# Inductance_meter.net
KiCad netlist of a schematic drawn in EAGLE
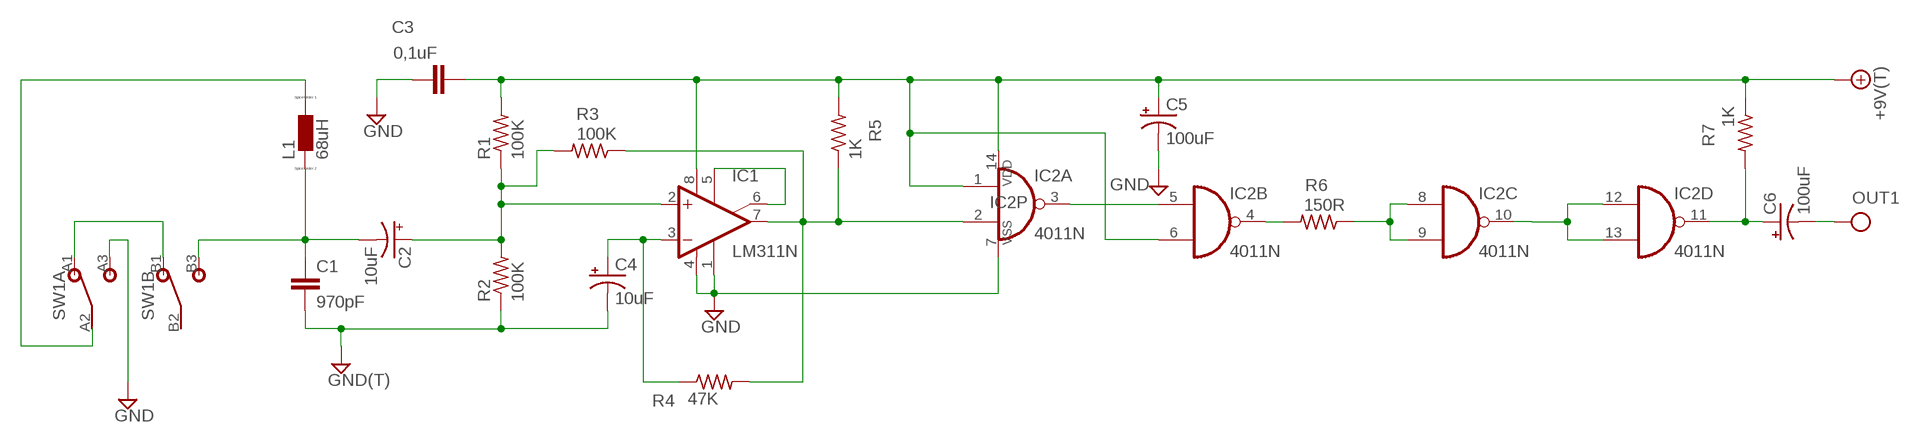
[diagram p0: schematic, sheet 1]

(export (version "E")
  (design (tool "Eeschema 10.0.6"))
  (components
    (comp (ref "+9V1")
      (value "+9V(T)")
      (footprint "eagle-import:SQUARE")
      (libsource (lib "eagle-import") (part "+9V(T)"))
    )
    (comp (ref "C1")
      (value "970pF")
      (footprint "eagle-import:072X025")
      (libsource (lib "eagle-import") (part "072X0252"))
    )
    (comp (ref "C2")
      (value "10uF")
      (footprint "eagle-import:050_020_2")
      (libsource (lib "eagle-import") (part "0502"))
    )
    (comp (ref "C3")
      (value "0,1uF")
      (footprint "eagle-import:072X025")
      (libsource (lib "eagle-import") (part "072X0252"))
    )
    (comp (ref "C4")
      (value "10uF")
      (footprint "eagle-import:050_020_2")
      (libsource (lib "eagle-import") (part "0502"))
    )
    (comp (ref "C5")
      (value "100uF")
      (footprint "eagle-import:050_020_2")
      (libsource (lib "eagle-import") (part "0502"))
    )
    (comp (ref "C6")
      (value "100uF")
      (footprint "eagle-import:050_020_2")
      (libsource (lib "eagle-import") (part "0502"))
    )
    (comp (ref "GND1")
      (value "GND(T)")
      (footprint "eagle-import:SQUARE")
      (libsource (lib "eagle-import") (part "GND(T)"))
    )
    (comp (ref "IC1")
      (value "LM311N")
      (footprint "eagle-import:DIL08")
      (libsource (lib "eagle-import") (part "LM311N"))
    )
    (comp (ref "IC2")
      (value "4011N")
      (footprint "eagle-import:DIL14")
      (libsource (lib "eagle-import") (part "4011N"))
    )
    (comp (ref "L1")
      (value "68uH")
      (footprint "eagle-import:0207_10")
      (libsource (lib "eagle-import") (part "L0207/10"))
    )
    (comp (ref "OUT1")
      (value "OUT(T)")
      (footprint "eagle-import:SQUARE")
      (libsource (lib "eagle-import") (part "OUT(T)"))
    )
    (comp (ref "R1")
      (value "100K")
      (footprint "eagle-import:R0207_3")
      (libsource (lib "eagle-import") (part "6MM.3"))
    )
    (comp (ref "R2")
      (value "100K")
      (footprint "eagle-import:R0207_3")
      (libsource (lib "eagle-import") (part "6MM.3"))
    )
    (comp (ref "R3")
      (value "100K")
      (footprint "eagle-import:R0207_3")
      (libsource (lib "eagle-import") (part "6MM.3"))
    )
    (comp (ref "R4")
      (value "47K")
      (footprint "eagle-import:R0207_3")
      (libsource (lib "eagle-import") (part "6MM.3"))
    )
    (comp (ref "R5")
      (value "1K")
      (footprint "eagle-import:R0207_3")
      (libsource (lib "eagle-import") (part "6MM.3"))
    )
    (comp (ref "R6")
      (value "150R")
      (footprint "eagle-import:R0207_3")
      (libsource (lib "eagle-import") (part "6MM.3"))
    )
    (comp (ref "R7")
      (value "1K")
      (footprint "eagle-import:R0207_3")
      (libsource (lib "eagle-import") (part "6MM.3"))
    )
    (comp (ref "SW1")
      (value "DPDT")
      (footprint "eagle-import:DPDT")
      (libsource (lib "eagle-import") (part "DPDT"))
    )
  )
  (nets
    (net (code "1") (name "+9V(T)") (class "Default")
      (node (ref "+9V1") (pin "1") (pinfunction "+9V_1") (pintype "power_in"))
      (node (ref "C3") (pin "2") (pinfunction "2_2") (pintype "passive"))
      (node (ref "C5") (pin "+") (pinfunction "+_+") (pintype "passive"))
      (node (ref "IC1") (pin "8") (pinfunction "V+_8") (pintype "power_in"))
      (node (ref "IC2") (pin "1") (pinfunction "I0_1") (pintype "input"))
      (node (ref "IC2") (pin "14") (pinfunction "VDD_14") (pintype "power_in"))
      (node (ref "IC2") (pin "6") (pinfunction "I1_6") (pintype "input"))
      (node (ref "R1") (pin "2") (pinfunction "2_2") (pintype "passive"))
      (node (ref "R5") (pin "2") (pinfunction "2_2") (pintype "passive"))
      (node (ref "R7") (pin "1") (pinfunction "1_1") (pintype "passive"))
    )
    (net (code "2") (name "GND") (class "Default")
      (node (ref "C1") (pin "2") (pinfunction "2_2") (pintype "passive"))
      (node (ref "C3") (pin "1") (pinfunction "1_1") (pintype "passive"))
      (node (ref "C4") (pin "-") (pinfunction "-_-") (pintype "passive"))
      (node (ref "C5") (pin "-") (pinfunction "-_-") (pintype "passive"))
      (node (ref "GND1") (pin "1") (pinfunction "GND_1") (pintype "power_in"))
      (node (ref "IC1") (pin "1") (pinfunction "GND_1") (pintype "passive"))
      (node (ref "IC1") (pin "4") (pinfunction "V-_4") (pintype "power_in"))
      (node (ref "IC2") (pin "7") (pinfunction "VSS_7") (pintype "power_in"))
      (node (ref "R2") (pin "1") (pinfunction "1_1") (pintype "passive"))
      (node (ref "SW1") (pin "A3") (pinfunction "3_A3") (pintype "passive"))
    )
    (net (code "3") (name "Net-(IC1-+IN)") (class "Default")
      (node (ref "C2") (pin "+") (pinfunction "+_+") (pintype "passive"))
      (node (ref "IC1") (pin "2") (pinfunction "+IN_2") (pintype "input"))
      (node (ref "R1") (pin "1") (pinfunction "1_1") (pintype "passive"))
      (node (ref "R2") (pin "2") (pinfunction "2_2") (pintype "passive"))
      (node (ref "R3") (pin "2") (pinfunction "2_2") (pintype "passive"))
    )
    (net (code "4") (name "Net-(IC1--IN)") (class "Default")
      (node (ref "C4") (pin "+") (pinfunction "+_+") (pintype "passive"))
      (node (ref "IC1") (pin "3") (pinfunction "-IN_3") (pintype "input"))
      (node (ref "R4") (pin "1") (pinfunction "1_1") (pintype "passive"))
    )
    (net (code "5") (name "Net-(IC1-ON)") (class "Default")
      (node (ref "IC1") (pin "5") (pinfunction "ON_5") (pintype "passive"))
      (node (ref "IC1") (pin "6") (pinfunction "ON/STR_6") (pintype "passive"))
    )
    (net (code "6") (name "Net-(IC1-OUT)") (class "Default")
      (node (ref "IC1") (pin "7") (pinfunction "OUT_7") (pintype "output"))
      (node (ref "IC2") (pin "2") (pinfunction "I1_2") (pintype "input"))
      (node (ref "R3") (pin "1") (pinfunction "1_1") (pintype "passive"))
      (node (ref "R4") (pin "2") (pinfunction "2_2") (pintype "passive"))
      (node (ref "R5") (pin "1") (pinfunction "1_1") (pintype "passive"))
    )
    (net (code "7") (name "Net-(IC2A-O)") (class "Default")
      (node (ref "IC2") (pin "3") (pinfunction "O_3") (pintype "output"))
      (node (ref "IC2") (pin "5") (pinfunction "I0_5") (pintype "input"))
    )
    (net (code "8") (name "Net-(IC2B-O)") (class "Default")
      (node (ref "IC2") (pin "4") (pinfunction "O_4") (pintype "output"))
      (node (ref "R6") (pin "2") (pinfunction "2_2") (pintype "passive"))
    )
    (net (code "9") (name "Net-(IC2C-I0)") (class "Default")
      (node (ref "IC2") (pin "8") (pinfunction "I0_8") (pintype "input"))
      (node (ref "IC2") (pin "9") (pinfunction "I1_9") (pintype "input"))
      (node (ref "R6") (pin "1") (pinfunction "1_1") (pintype "passive"))
    )
    (net (code "10") (name "Net-(IC2C-O)") (class "Default")
      (node (ref "IC2") (pin "10") (pinfunction "O_10") (pintype "output"))
      (node (ref "IC2") (pin "12") (pinfunction "I0_12") (pintype "input"))
      (node (ref "IC2") (pin "13") (pinfunction "I1_13") (pintype "input"))
    )
    (net (code "11") (name "Net-(IC2D-O)") (class "Default")
      (node (ref "C6") (pin "+") (pinfunction "+_+") (pintype "passive"))
      (node (ref "IC2") (pin "11") (pinfunction "O_11") (pintype "output"))
      (node (ref "R7") (pin "2") (pinfunction "2_2") (pintype "passive"))
    )
    (net (code "12") (name "Net-(SW1A-1)") (class "Default")
      (node (ref "SW1") (pin "A1") (pinfunction "1_A1") (pintype "passive"))
      (node (ref "SW1") (pin "B1") (pinfunction "1_B1") (pintype "passive"))
    )
    (net (code "13") (name "Net-(SW1A-2)") (class "Default")
      (node (ref "L1") (pin "1") (pinfunction "1_1") (pintype "passive"))
      (node (ref "SW1") (pin "A2") (pinfunction "2_A2") (pintype "passive"))
    )
    (net (code "14") (name "Net-(SW1B-3)") (class "Default")
      (node (ref "C1") (pin "1") (pinfunction "1_1") (pintype "passive"))
      (node (ref "C2") (pin "-") (pinfunction "-_-") (pintype "passive"))
      (node (ref "L1") (pin "2") (pinfunction "2_2") (pintype "passive"))
      (node (ref "SW1") (pin "B3") (pinfunction "3_B3") (pintype "passive"))
    )
    (net (code "15") (name "OUT(T)") (class "Default")
      (node (ref "C6") (pin "-") (pinfunction "-_-") (pintype "passive"))
      (node (ref "OUT1") (pin "1") (pinfunction "OUT_1") (pintype "power_in"))
    )
    (net (code "16") (name "unconnected-(SW1B-2-PadB2)") (class "Default")
      (node (ref "SW1") (pin "B2") (pinfunction "2_B2") (pintype "passive"))
    )
  )
)
